# LM317T_sema.net
KiCad netlist of a schematic drawn in Altium Designer
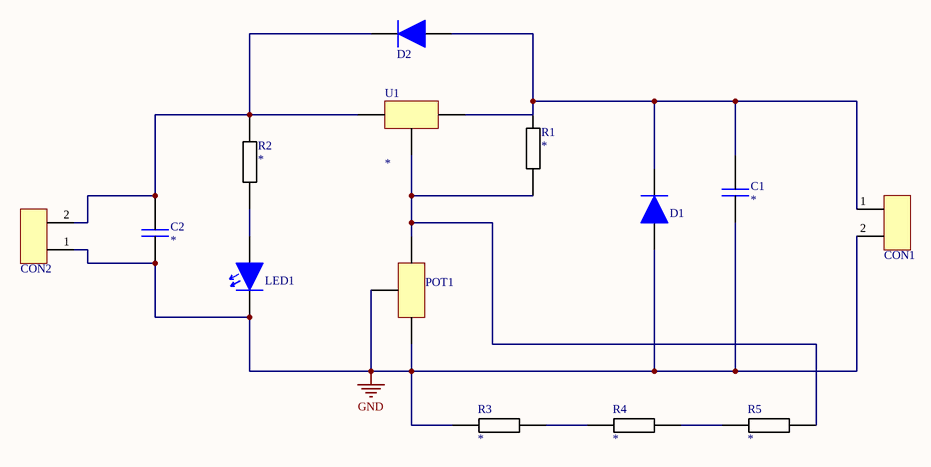
[diagram p0: LM317T_sema.SchDoc]

(export (version "E")
  (design (tool "Eeschema 10.0.6"))
  (components
    (comp (ref "C1")
      (value "Film")
      (footprint "CAP_Film")
      (fields
        (field (name "MANUFACTURER") "Nichicon")
        (field (name "MANUFACTURER PART NUMBER") "UCY2G150MPD")
        (field (name "ALTIUM_VALUE") "*")
      )
      (libsource (lib "Integrated_Library_genel") (part "CAP_Film"))
    )
    (comp (ref "C2")
      (value "Film")
      (footprint "CAP_Film")
      (fields
        (field (name "MANUFACTURER") "Nichicon")
        (field (name "MANUFACTURER PART NUMBER") "UCY2G150MPD")
        (field (name "ALTIUM_VALUE") "*")
      )
      (libsource (lib "Integrated_Library_genel") (part "CAP_Film"))
    )
    (comp (ref "CON1")
      (value "CONNECTOR*2")
      (footprint "CONNECTOR*2")
      (libsource (lib "") (part "CONNECTOR*2_1"))
    )
    (comp (ref "CON2")
      (value "CONNECTOR*2")
      (footprint "CONNECTOR*2")
      (libsource (lib "Integrated_Library_genel") (part "CONNECTOR*2"))
    )
    (comp (ref "D1")
      (value "1N4001")
      (footprint "1N4001 Diyot")
      (libsource (lib "Integrated_Library_genel") (part "1N4001 Diyot"))
    )
    (comp (ref "D2")
      (value "1N4001")
      (footprint "1N4001 Diyot")
      (libsource (lib "Integrated_Library_genel") (part "1N4001 Diyot"))
    )
    (comp (ref "LED1")
      (value "LED")
      (footprint "LED")
      (libsource (lib "Integrated_Library_genel") (part "LED"))
    )
    (comp (ref "POT1")
      (value "POT")
      (footprint "POT")
      (libsource (lib "Integrated_Library_genel") (part "POT"))
    )
    (comp (ref "R1")
      (value "RES_1/4W")
      (footprint "RES_1/4W")
      (fields (field (name "ALTIUM_VALUE") "*"))
      (libsource (lib "Integrated_Library_genel") (part "RES_1/4W"))
    )
    (comp (ref "R2")
      (value "RES_1/4W")
      (footprint "RES_1/4W")
      (fields (field (name "ALTIUM_VALUE") "*"))
      (libsource (lib "Integrated_Library_genel") (part "RES_1/4W"))
    )
    (comp (ref "R3")
      (value "RES_1/4W")
      (footprint "RES_1/4W")
      (fields (field (name "ALTIUM_VALUE") "*"))
      (libsource (lib "Integrated_Library_genel") (part "RES_1/4W"))
    )
    (comp (ref "R4")
      (value "RES_1/4W")
      (footprint "RES_1/4W")
      (fields (field (name "ALTIUM_VALUE") "*"))
      (libsource (lib "Integrated_Library_genel") (part "RES_1/4W"))
    )
    (comp (ref "R5")
      (value "RES_1/4W")
      (footprint "RES_1/4W")
      (fields (field (name "ALTIUM_VALUE") "*"))
      (libsource (lib "Integrated_Library_genel") (part "RES_1/4W"))
    )
    (comp (ref "U1")
      (value "TO-220")
      (footprint "TO-220")
      (fields (field (name "NAME") "*"))
      (libsource (lib "Integrated_Library_genel") (part "TO-220"))
    )
  )
  (nets
    (net (code "1") (name "GND") (class "Default")
      (node (ref "C1") (pin "1") (pinfunction "1_1") (pintype "passive"))
      (node (ref "C2") (pin "1") (pinfunction "1_1") (pintype "passive"))
      (node (ref "CON1") (pin "2") (pinfunction "2_2") (pintype "power_in"))
      (node (ref "CON2") (pin "1") (pinfunction "1_1") (pintype "power_in"))
      (node (ref "D1") (pin "2") (pinfunction "2_2") (pintype "passive"))
      (node (ref "LED1") (pin "2") (pinfunction "2_2") (pintype "passive"))
      (node (ref "POT1") (pin "1") (pinfunction "1_1") (pintype "passive"))
      (node (ref "POT1") (pin "2") (pinfunction "2_2") (pintype "passive"))
      (node (ref "R3") (pin "1") (pinfunction "1_1") (pintype "passive"))
    )
    (net (code "2") (name "Net-(C1-Pad2)") (class "Default")
      (node (ref "C1") (pin "2") (pinfunction "2_2") (pintype "passive"))
      (node (ref "CON1") (pin "1") (pinfunction "1_1") (pintype "power_in"))
      (node (ref "D1") (pin "1") (pinfunction "1_1") (pintype "passive"))
      (node (ref "D2") (pin "2") (pinfunction "2_2") (pintype "passive"))
      (node (ref "R1") (pin "2") (pinfunction "2_2") (pintype "passive"))
      (node (ref "U1") (pin "2") (pinfunction "2_2") (pintype "passive"))
    )
    (net (code "3") (name "Net-(C2-Pad2)") (class "Default")
      (node (ref "C2") (pin "2") (pinfunction "2_2") (pintype "passive"))
      (node (ref "CON2") (pin "2") (pinfunction "2_2") (pintype "power_in"))
      (node (ref "D2") (pin "1") (pinfunction "1_1") (pintype "passive"))
      (node (ref "R2") (pin "2") (pinfunction "2_2") (pintype "passive"))
      (node (ref "U1") (pin "3") (pinfunction "3_3") (pintype "passive"))
    )
    (net (code "4") (name "Net-(LED1-Pad1)") (class "Default")
      (node (ref "LED1") (pin "1") (pinfunction "1_1") (pintype "passive"))
      (node (ref "R2") (pin "1") (pinfunction "1_1") (pintype "passive"))
    )
    (net (code "5") (name "Net-(POT1-Pad3)") (class "Default")
      (node (ref "POT1") (pin "3") (pinfunction "3_3") (pintype "passive"))
      (node (ref "R1") (pin "1") (pinfunction "1_1") (pintype "passive"))
      (node (ref "R5") (pin "2") (pinfunction "2_2") (pintype "passive"))
      (node (ref "U1") (pin "1") (pinfunction "1_1") (pintype "passive"))
    )
    (net (code "6") (name "Net-(R3-Pad2)") (class "Default")
      (node (ref "R3") (pin "2") (pinfunction "2_2") (pintype "passive"))
      (node (ref "R4") (pin "1") (pinfunction "1_1") (pintype "passive"))
    )
    (net (code "7") (name "Net-(R4-Pad2)") (class "Default")
      (node (ref "R4") (pin "2") (pinfunction "2_2") (pintype "passive"))
      (node (ref "R5") (pin "1") (pinfunction "1_1") (pintype "passive"))
    )
  )
)
